# Adafruit_ADS1115_ADC_STEMMA_QT.net
KiCad netlist of a schematic drawn in EAGLE
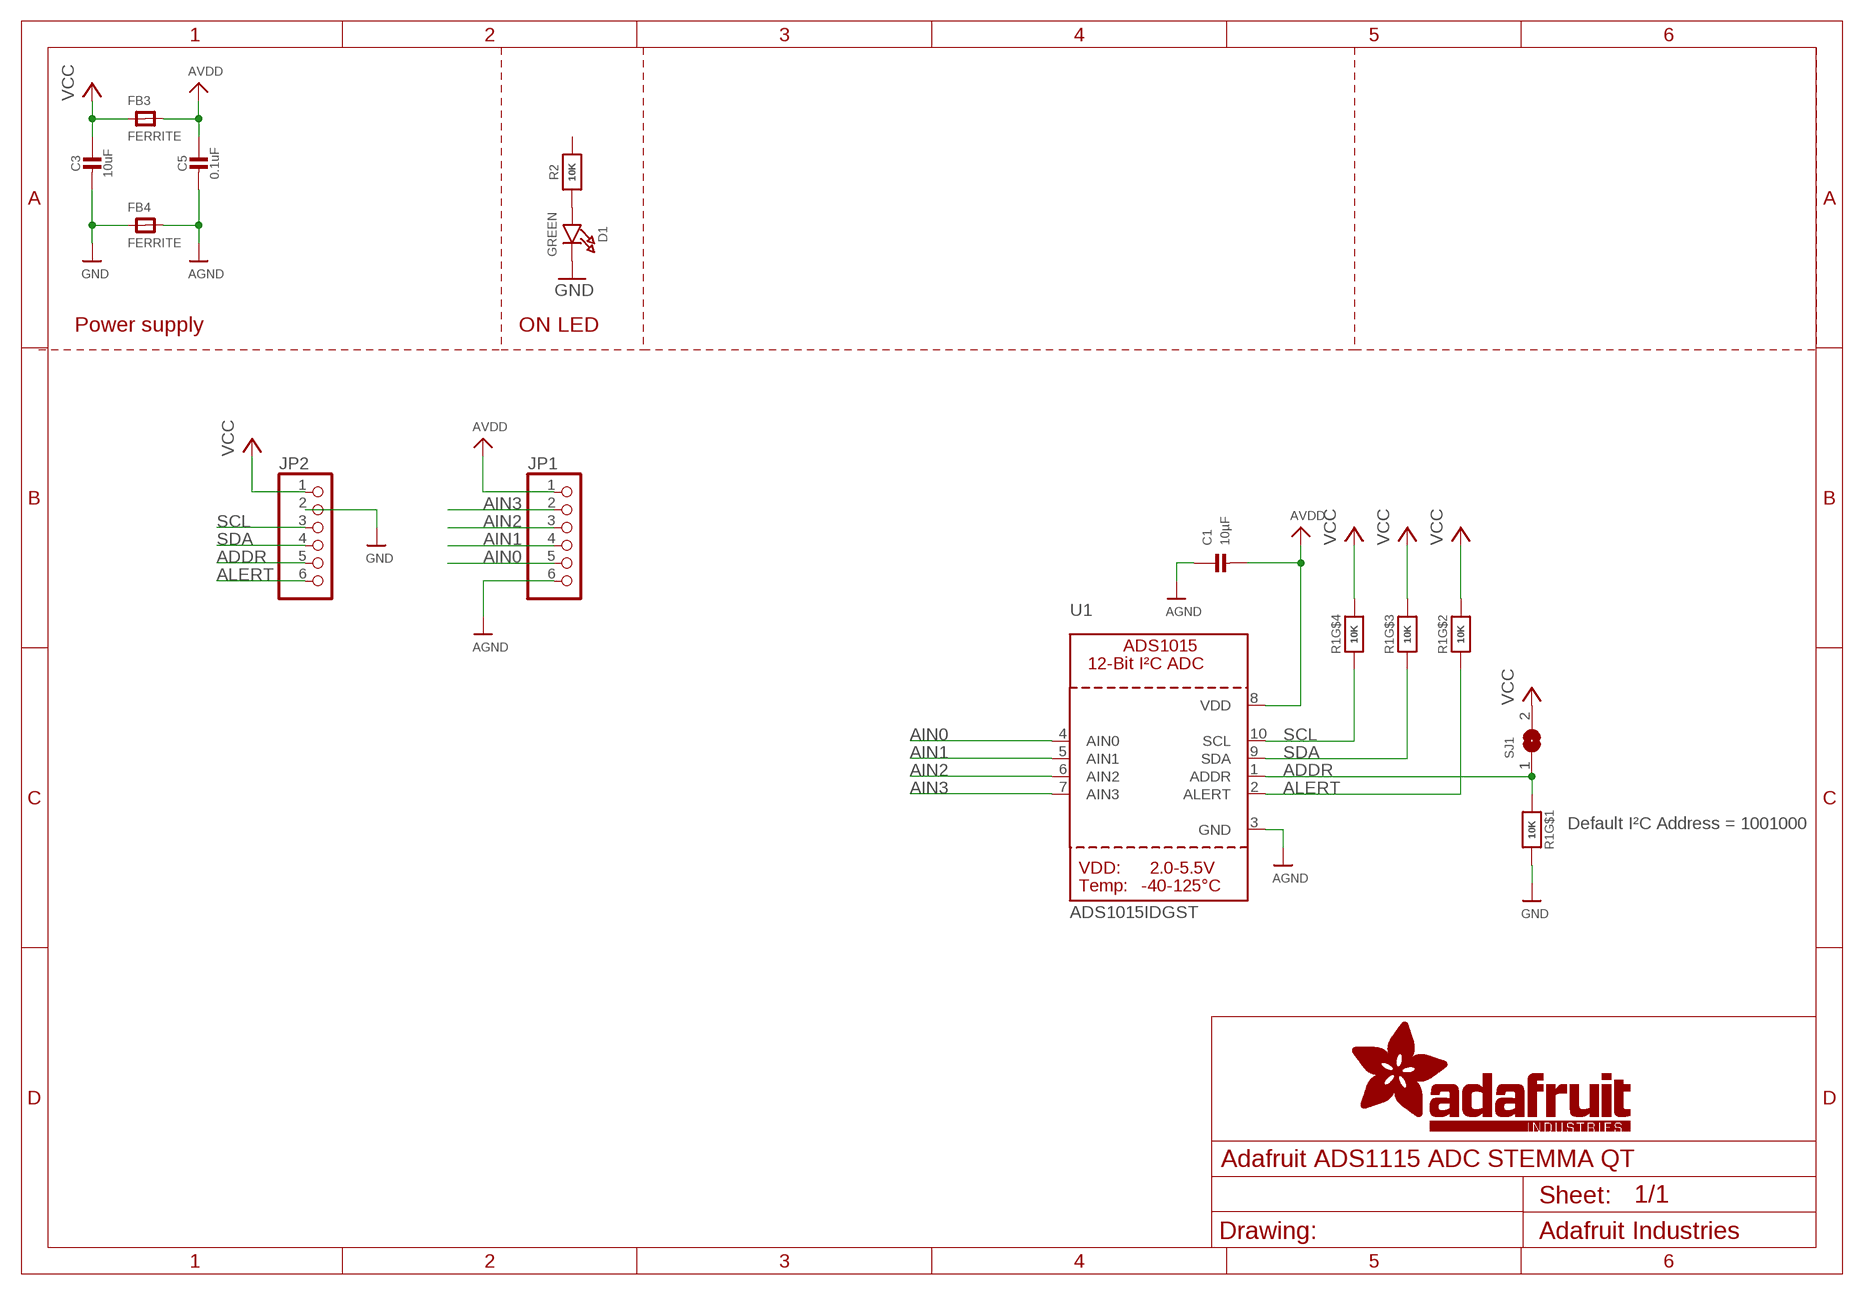
[diagram p0: schematic, sheet 1]

(export (version "E")
  (design (tool "Eeschema 10.0.6"))
  (components
    (comp (ref "C1")
      (value "10µF")
      (footprint "eagle-import:0805-NO")
      (libsource (lib "eagle-import") (part "CAP_CERAMIC0805-NOOUTLINE"))
    )
    (comp (ref "C3")
      (value "10uF")
      (footprint "eagle-import:0805-NO")
      (libsource (lib "eagle-import") (part "CAP_CERAMIC0805-NOOUTLINE"))
    )
    (comp (ref "C5")
      (value "0.1uF")
      (footprint "eagle-import:0603-NO")
      (libsource (lib "eagle-import") (part "CAP_CERAMIC0603_NO"))
    )
    (comp (ref "D1")
      (value "GREEN")
      (footprint "eagle-import:CHIPLED_0603_NOOUTLINE")
      (libsource (lib "eagle-import") (part "LED0603_NOOUTLINE"))
    )
    (comp (ref "FB3")
      (value "FERRITE")
      (footprint "eagle-import:0603-NO")
      (libsource (lib "eagle-import") (part "FERRITE-0603NO"))
    )
    (comp (ref "FB4")
      (value "FERRITE")
      (footprint "eagle-import:0603-NO")
      (libsource (lib "eagle-import") (part "FERRITE-0603NO"))
    )
    (comp (ref "JP1")
      (value "HEADER-1X670MIL")
      (footprint "eagle-import:1X06_ROUND_70")
      (libsource (lib "eagle-import") (part "HEADER-1X670MIL"))
    )
    (comp (ref "JP2")
      (value "HEADER-1X670MIL")
      (footprint "eagle-import:1X06_ROUND_70")
      (libsource (lib "eagle-import") (part "HEADER-1X670MIL"))
    )
    (comp (ref "R1")
      (value "10K")
      (footprint "eagle-import:RESPACK_4X0603")
      (libsource (lib "eagle-import") (part "RESISTOR_4PACK"))
    )
    (comp (ref "R2")
      (value "10K")
      (footprint "eagle-import:0603-NO")
      (libsource (lib "eagle-import") (part "RESISTOR_0603_NOOUT"))
    )
    (comp (ref "SJ1")
      (value "SOLDERJUMPER")
      (footprint "eagle-import:SOLDERJUMPER_ARROW_NOPASTE")
      (libsource (lib "eagle-import") (part "SOLDERJUMPER"))
    )
    (comp (ref "U1")
      (value "ADS1015IDGST")
      (footprint "eagle-import:MSOP10")
      (libsource (lib "eagle-import") (part "ADC_ADS1015"))
    )
  )
  (nets
    (net (code "1") (name "/ADDR") (class "Default")
      (node (ref "JP2") (pin "5") (pinfunction "5_5") (pintype "passive"))
      (node (ref "R1") (pin "1") (pinfunction "1_1") (pintype "passive"))
      (node (ref "SJ1") (pin "1") (pinfunction "1_1") (pintype "passive"))
      (node (ref "U1") (pin "1") (pinfunction "ADDR_1") (pintype "bidirectional"))
    )
    (net (code "2") (name "/AIN0") (class "Default")
      (node (ref "JP1") (pin "5") (pinfunction "5_5") (pintype "passive"))
      (node (ref "U1") (pin "4") (pinfunction "AIN0_4") (pintype "bidirectional"))
    )
    (net (code "3") (name "/AIN1") (class "Default")
      (node (ref "JP1") (pin "4") (pinfunction "4_4") (pintype "passive"))
      (node (ref "U1") (pin "5") (pinfunction "AIN1_5") (pintype "bidirectional"))
    )
    (net (code "4") (name "/AIN2") (class "Default")
      (node (ref "JP1") (pin "3") (pinfunction "3_3") (pintype "passive"))
      (node (ref "U1") (pin "6") (pinfunction "AIN2_6") (pintype "bidirectional"))
    )
    (net (code "5") (name "/AIN3") (class "Default")
      (node (ref "JP1") (pin "2") (pinfunction "2_2") (pintype "passive"))
      (node (ref "U1") (pin "7") (pinfunction "AIN3_7") (pintype "bidirectional"))
    )
    (net (code "6") (name "/ALERT") (class "Default")
      (node (ref "JP2") (pin "6") (pinfunction "6_6") (pintype "passive"))
      (node (ref "R1") (pin "2") (pinfunction "1_2") (pintype "passive"))
      (node (ref "U1") (pin "2") (pinfunction "ALERT_2") (pintype "bidirectional"))
    )
    (net (code "7") (name "/SCL") (class "Default")
      (node (ref "JP2") (pin "3") (pinfunction "3_3") (pintype "passive"))
      (node (ref "R1") (pin "4") (pinfunction "1_4") (pintype "passive"))
      (node (ref "U1") (pin "10") (pinfunction "SCL_10") (pintype "bidirectional"))
    )
    (net (code "8") (name "/SDA") (class "Default")
      (node (ref "JP2") (pin "4") (pinfunction "4_4") (pintype "passive"))
      (node (ref "R1") (pin "3") (pinfunction "1_3") (pintype "passive"))
      (node (ref "U1") (pin "9") (pinfunction "SDA_9") (pintype "bidirectional"))
    )
    (net (code "9") (name "AGND") (class "Default")
      (node (ref "C1") (pin "1") (pinfunction "1_1") (pintype "passive"))
      (node (ref "C5") (pin "2") (pinfunction "2_2") (pintype "passive"))
      (node (ref "FB4") (pin "2") (pinfunction "P$2_2") (pintype "passive"))
      (node (ref "JP1") (pin "6") (pinfunction "6_6") (pintype "passive"))
      (node (ref "U1") (pin "3") (pinfunction "GND_3") (pintype "bidirectional"))
    )
    (net (code "10") (name "AVDD") (class "Default")
      (node (ref "C1") (pin "2") (pinfunction "2_2") (pintype "passive"))
      (node (ref "C5") (pin "1") (pinfunction "1_1") (pintype "passive"))
      (node (ref "FB3") (pin "2") (pinfunction "P$2_2") (pintype "passive"))
      (node (ref "JP1") (pin "1") (pinfunction "1_1") (pintype "passive"))
      (node (ref "U1") (pin "8") (pinfunction "VDD_8") (pintype "bidirectional"))
    )
    (net (code "11") (name "GND") (class "Default")
      (node (ref "C3") (pin "2") (pinfunction "2_2") (pintype "passive"))
      (node (ref "D1") (pin "C") (pinfunction "C_C") (pintype "passive"))
      (node (ref "FB4") (pin "1") (pinfunction "P$1_1") (pintype "passive"))
      (node (ref "JP2") (pin "2") (pinfunction "2_2") (pintype "passive"))
      (node (ref "R1") (pin "8") (pinfunction "2_8") (pintype "passive"))
    )
    (net (code "12") (name "Net-(D1-PadA)") (class "Default")
      (node (ref "D1") (pin "A") (pinfunction "A_A") (pintype "passive"))
      (node (ref "R2") (pin "1") (pinfunction "1_1") (pintype "passive"))
    )
    (net (code "13") (name "VCC") (class "Default")
      (node (ref "C3") (pin "1") (pinfunction "1_1") (pintype "passive"))
      (node (ref "FB3") (pin "1") (pinfunction "P$1_1") (pintype "passive"))
      (node (ref "JP2") (pin "1") (pinfunction "1_1") (pintype "passive"))
      (node (ref "R1") (pin "5") (pinfunction "2_5") (pintype "passive"))
      (node (ref "R1") (pin "6") (pinfunction "2_6") (pintype "passive"))
      (node (ref "R1") (pin "7") (pinfunction "2_7") (pintype "passive"))
      (node (ref "SJ1") (pin "2") (pinfunction "2_2") (pintype "passive"))
    )
    (net (code "14") (name "unconnected-(R2-Pad2)") (class "Default")
      (node (ref "R2") (pin "2") (pinfunction "2_2") (pintype "passive"))
    )
  )
)
